# design.net
KiCad netlist of a schematic drawn in EasyEDA Pro
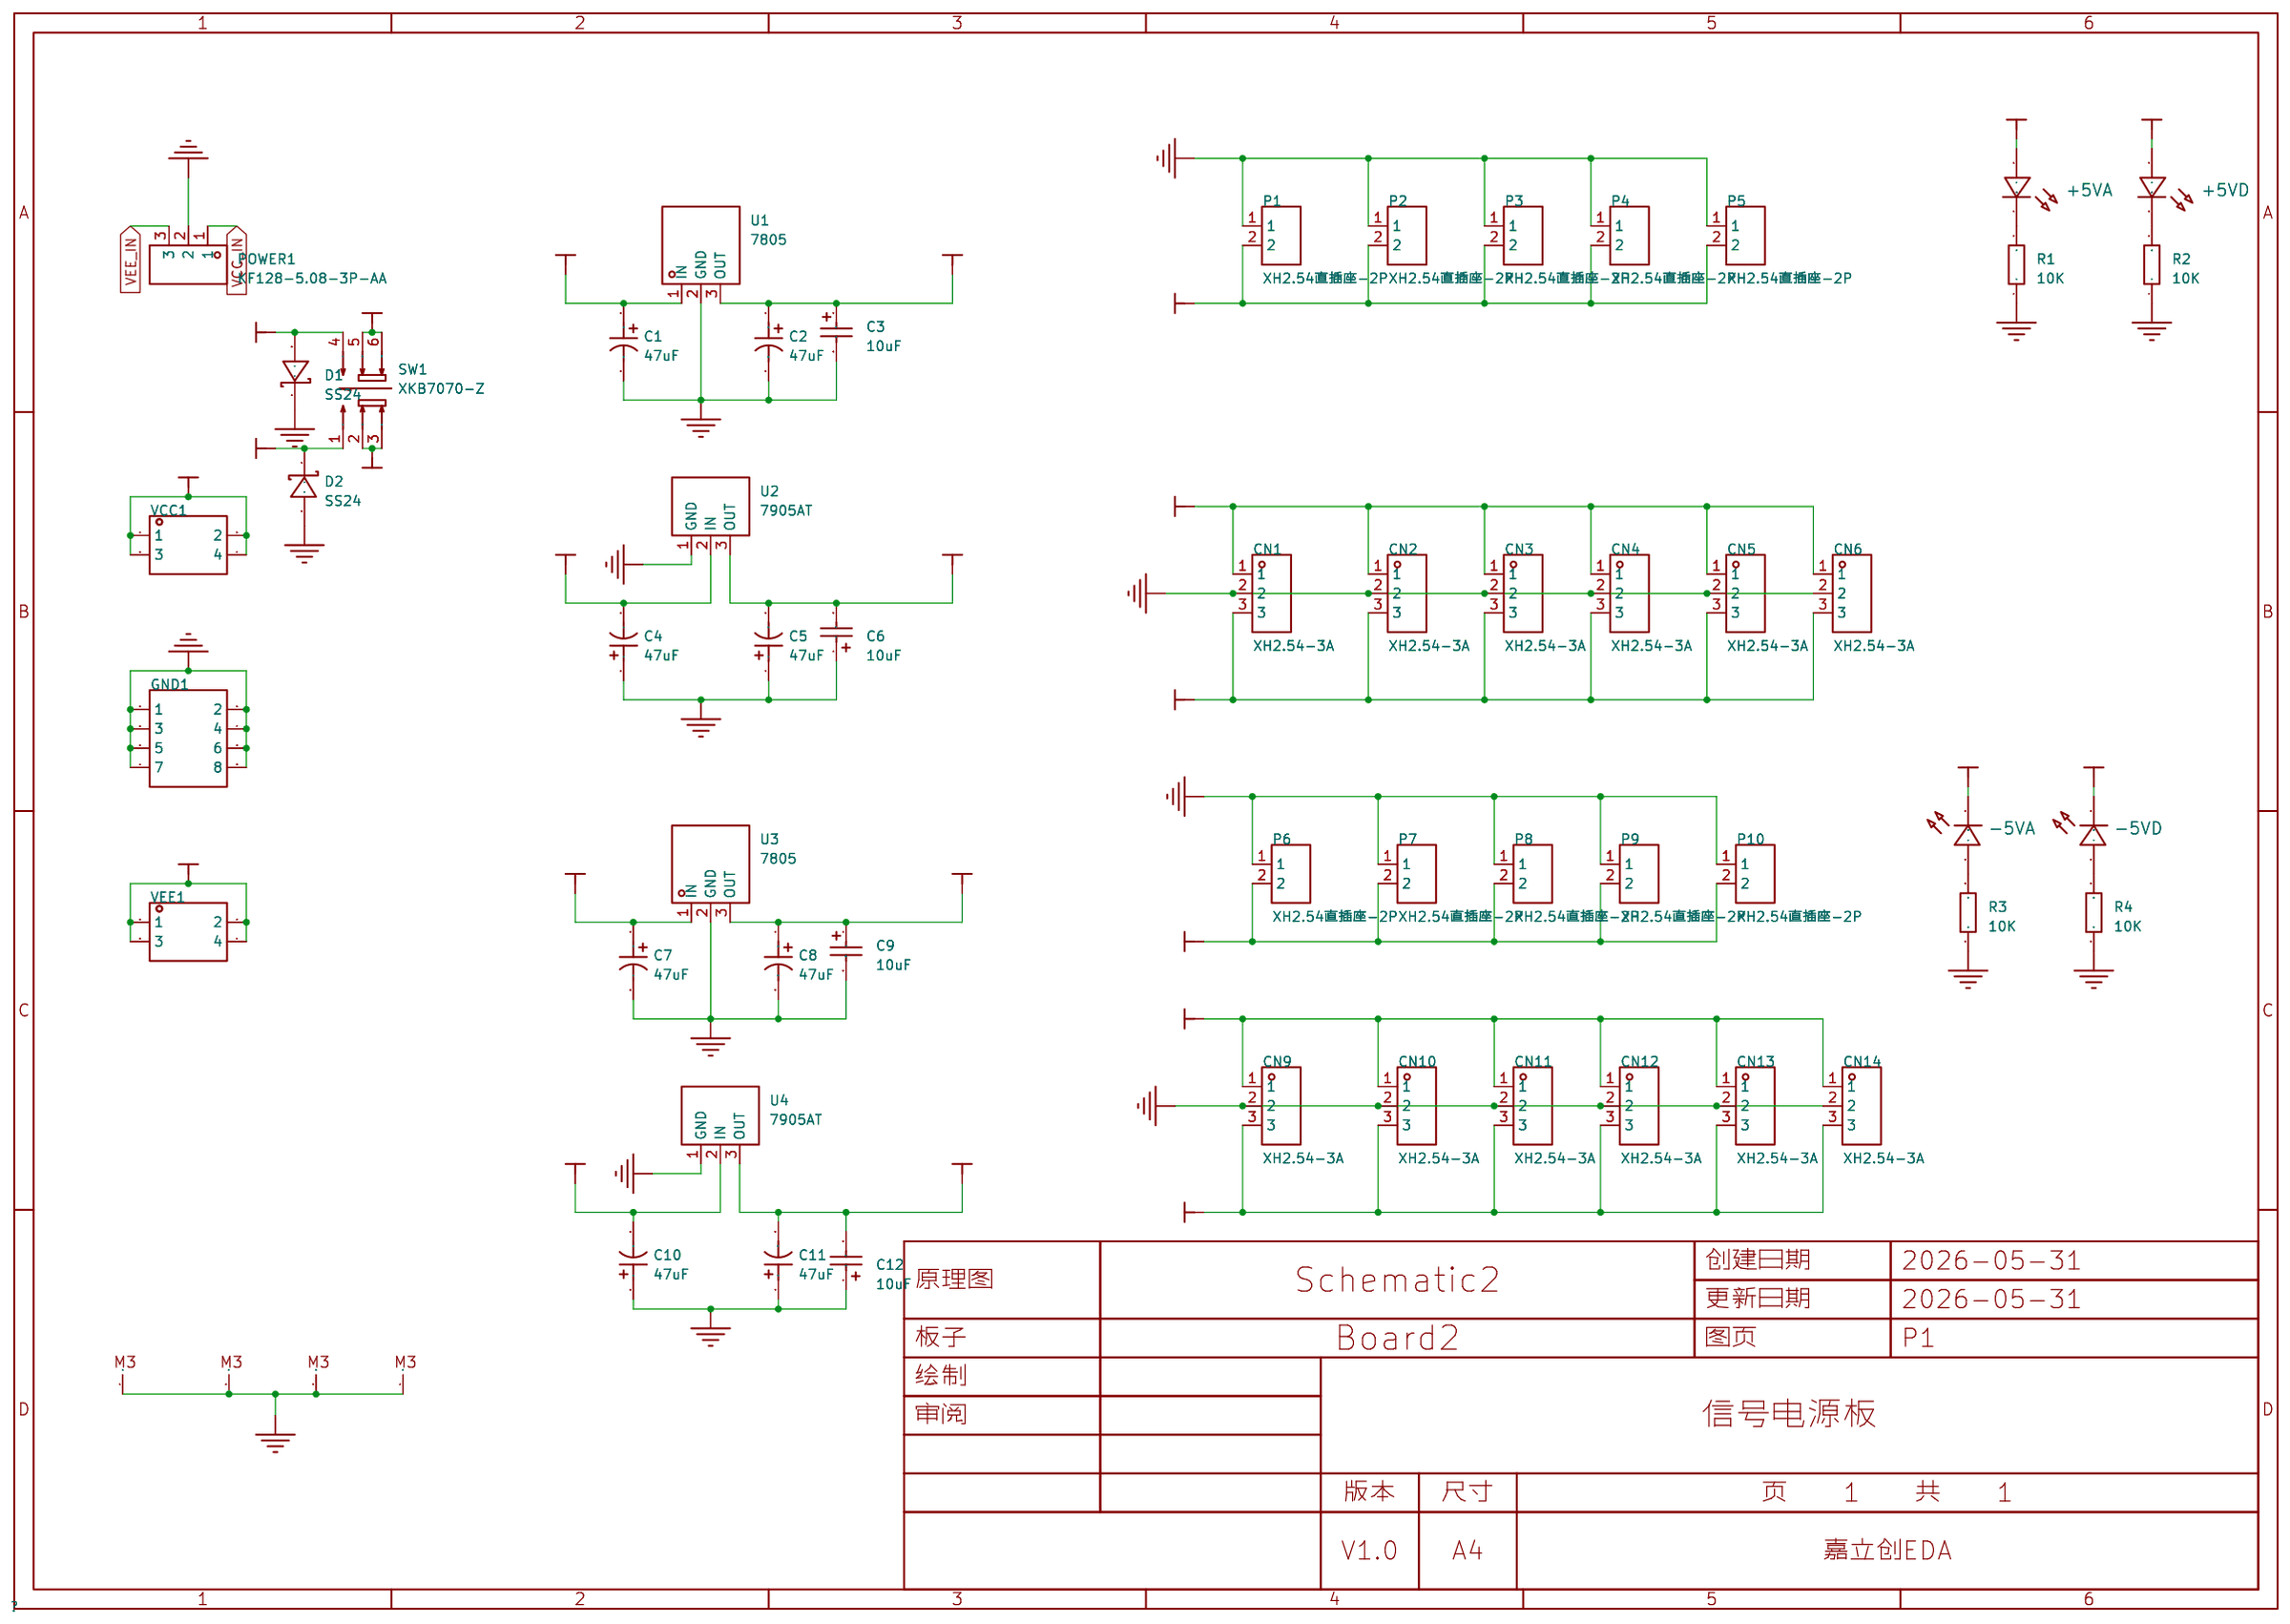
[diagram p0: schematic sheet]

(export (version "E")
  (design (tool "Eeschema 10.0.6"))
  (components
    (comp (ref "+5VA")
      (value "~")
      (footprint "easyedapro:LED_0603")
      (libsource (lib "easyedapro") (part "LED_R"))
    )
    (comp (ref "+5VD")
      (value "~")
      (footprint "easyedapro:LED_0603")
      (libsource (lib "easyedapro") (part "LED_R"))
    )
    (comp (ref "-5VA")
      (value "~")
      (footprint "easyedapro:LED_0603")
      (libsource (lib "easyedapro") (part "LED_R"))
    )
    (comp (ref "-5VD")
      (value "~")
      (footprint "easyedapro:LED_0603")
      (libsource (lib "easyedapro") (part "LED_R"))
    )
    (comp (ref "C1")
      (value "47uF")
      (footprint "easyedapro:CAP-SMD_BD6.3-L6.6-W6.6-LS7.3-FD")
      (fields (field (name "Manufacturer Part") "126RV0104") (field (name "Manufacturer") "KNSCHA(科尼盛)"))
      (libsource (lib "easyedapro") (part "126RV0104"))
    )
    (comp (ref "C2")
      (value "47uF")
      (footprint "easyedapro:CAP-SMD_BD6.3-L6.6-W6.6-LS7.3-FD")
      (fields (field (name "Manufacturer Part") "126RV0104") (field (name "Manufacturer") "KNSCHA(科尼盛)"))
      (libsource (lib "easyedapro") (part "126RV0104"))
    )
    (comp (ref "C3")
      (value "10uF")
      (footprint "easyedapro:CAP-SMD_L3.2-W1.6-RD-C7171")
      (fields (field (name "Manufacturer Part") "TAJA106K016RNJ") (field (name "Manufacturer") "Kyocera AVX"))
      (libsource (lib "easyedapro") (part "TAJA106K016RNJ"))
    )
    (comp (ref "C4")
      (value "47uF")
      (footprint "easyedapro:CAP-SMD_BD6.3-L6.6-W6.6-LS7.3-FD")
      (fields (field (name "Manufacturer Part") "126RV0104") (field (name "Manufacturer") "KNSCHA(科尼盛)"))
      (libsource (lib "easyedapro") (part "126RV0104"))
    )
    (comp (ref "C5")
      (value "47uF")
      (footprint "easyedapro:CAP-SMD_BD6.3-L6.6-W6.6-LS7.3-FD")
      (fields (field (name "Manufacturer Part") "126RV0104") (field (name "Manufacturer") "KNSCHA(科尼盛)"))
      (libsource (lib "easyedapro") (part "126RV0104"))
    )
    (comp (ref "C6")
      (value "10uF")
      (footprint "easyedapro:CAP-SMD_L3.2-W1.6-RD-C7171")
      (fields (field (name "Manufacturer Part") "TAJA106K016RNJ") (field (name "Manufacturer") "Kyocera AVX"))
      (libsource (lib "easyedapro") (part "TAJA106K016RNJ"))
    )
    (comp (ref "C7")
      (value "47uF")
      (footprint "easyedapro:CAP-SMD_BD6.3-L6.6-W6.6-LS7.3-FD")
      (fields (field (name "Manufacturer Part") "126RV0104") (field (name "Manufacturer") "KNSCHA(科尼盛)"))
      (libsource (lib "easyedapro") (part "126RV0104"))
    )
    (comp (ref "C8")
      (value "47uF")
      (footprint "easyedapro:CAP-SMD_BD6.3-L6.6-W6.6-LS7.3-FD")
      (fields (field (name "Manufacturer Part") "126RV0104") (field (name "Manufacturer") "KNSCHA(科尼盛)"))
      (libsource (lib "easyedapro") (part "126RV0104"))
    )
    (comp (ref "C9")
      (value "10uF")
      (footprint "easyedapro:CAP-SMD_L3.2-W1.6-RD-C7171")
      (fields (field (name "Manufacturer Part") "TAJA106K016RNJ") (field (name "Manufacturer") "Kyocera AVX"))
      (libsource (lib "easyedapro") (part "TAJA106K016RNJ"))
    )
    (comp (ref "C10")
      (value "47uF")
      (footprint "easyedapro:CAP-SMD_BD6.3-L6.6-W6.6-LS7.3-FD")
      (fields (field (name "Manufacturer Part") "126RV0104") (field (name "Manufacturer") "KNSCHA(科尼盛)"))
      (libsource (lib "easyedapro") (part "126RV0104"))
    )
    (comp (ref "C11")
      (value "47uF")
      (footprint "easyedapro:CAP-SMD_BD6.3-L6.6-W6.6-LS7.3-FD")
      (fields (field (name "Manufacturer Part") "126RV0104") (field (name "Manufacturer") "KNSCHA(科尼盛)"))
      (libsource (lib "easyedapro") (part "126RV0104"))
    )
    (comp (ref "C12")
      (value "10uF")
      (footprint "easyedapro:CAP-SMD_L3.2-W1.6-RD-C7171")
      (fields (field (name "Manufacturer Part") "TAJA106K016RNJ") (field (name "Manufacturer") "Kyocera AVX"))
      (libsource (lib "easyedapro") (part "TAJA106K016RNJ"))
    )
    (comp (ref "CN1")
      (value "XH2.54-3A")
      (footprint "easyedapro:CONN-TH_3P-P2.50_HCTL_XH-3A-L")
      (libsource (lib "easyedapro") (part "XH2.54-3A"))
    )
    (comp (ref "CN2")
      (value "XH2.54-3A")
      (footprint "easyedapro:CONN-TH_3P-P2.50_HCTL_XH-3A-L")
      (libsource (lib "easyedapro") (part "XH2.54-3A"))
    )
    (comp (ref "CN3")
      (value "XH2.54-3A")
      (footprint "easyedapro:CONN-TH_3P-P2.50_HCTL_XH-3A-L")
      (libsource (lib "easyedapro") (part "XH2.54-3A"))
    )
    (comp (ref "CN4")
      (value "XH2.54-3A")
      (footprint "easyedapro:CONN-TH_3P-P2.50_HCTL_XH-3A-L")
      (libsource (lib "easyedapro") (part "XH2.54-3A"))
    )
    (comp (ref "CN5")
      (value "XH2.54-3A")
      (footprint "easyedapro:CONN-TH_3P-P2.50_HCTL_XH-3A-L")
      (libsource (lib "easyedapro") (part "XH2.54-3A"))
    )
    (comp (ref "CN6")
      (value "XH2.54-3A")
      (footprint "easyedapro:CONN-TH_3P-P2.50_HCTL_XH-3A-L")
      (libsource (lib "easyedapro") (part "XH2.54-3A"))
    )
    (comp (ref "CN9")
      (value "XH2.54-3A")
      (footprint "easyedapro:CONN-TH_3P-P2.50_HCTL_XH-3A-L")
      (libsource (lib "easyedapro") (part "XH2.54-3A"))
    )
    (comp (ref "CN10")
      (value "XH2.54-3A")
      (footprint "easyedapro:CONN-TH_3P-P2.50_HCTL_XH-3A-L")
      (libsource (lib "easyedapro") (part "XH2.54-3A"))
    )
    (comp (ref "CN11")
      (value "XH2.54-3A")
      (footprint "easyedapro:CONN-TH_3P-P2.50_HCTL_XH-3A-L")
      (libsource (lib "easyedapro") (part "XH2.54-3A"))
    )
    (comp (ref "CN12")
      (value "XH2.54-3A")
      (footprint "easyedapro:CONN-TH_3P-P2.50_HCTL_XH-3A-L")
      (libsource (lib "easyedapro") (part "XH2.54-3A"))
    )
    (comp (ref "CN13")
      (value "XH2.54-3A")
      (footprint "easyedapro:CONN-TH_3P-P2.50_HCTL_XH-3A-L")
      (libsource (lib "easyedapro") (part "XH2.54-3A"))
    )
    (comp (ref "CN14")
      (value "XH2.54-3A")
      (footprint "easyedapro:CONN-TH_3P-P2.50_HCTL_XH-3A-L")
      (libsource (lib "easyedapro") (part "XH2.54-3A"))
    )
    (comp (ref "D1")
      (value "SS24")
      (footprint "easyedapro:SMA_L4.3-W2.6-LS5.2-RD")
      (description "正向压降(Vf):550mV@2A;直流反向耐压(Vr):40V;平均整流电流(Io):2A;")
      (libsource (lib "easyedapro") (part "SS24_C13444"))
    )
    (comp (ref "D2")
      (value "SS24")
      (footprint "easyedapro:SMA_L4.3-W2.6-LS5.2-RD")
      (description "正向压降(Vf):550mV@2A;直流反向耐压(Vr):40V;平均整流电流(Io):2A;")
      (libsource (lib "easyedapro") (part "SS24_C13444"))
    )
    (comp (ref "GND1")
      (value "~")
      (footprint "easyedapro:HDR-TH_8P-P2.54-V-F-R2-C4-S2.54-1")
      (libsource (lib "easyedapro") (part "HDR-F-2.54_2x4"))
    )
    (comp (ref "M1") (value "~") (footprint "easyedapro:M3") (libsource (lib "easyedapro") (part "螺丝孔")))
    (comp (ref "M2") (value "~") (footprint "easyedapro:M3") (libsource (lib "easyedapro") (part "螺丝孔")))
    (comp (ref "M3") (value "~") (footprint "easyedapro:M3") (libsource (lib "easyedapro") (part "螺丝孔")))
    (comp (ref "M4") (value "~") (footprint "easyedapro:M3") (libsource (lib "easyedapro") (part "螺丝孔")))
    (comp (ref "P1")
      (value "XH2.54直插座-2P")
      (footprint "easyedapro:CONN-TH_XH2.54-2P")
      (libsource (lib "easyedapro") (part "XH2.54直插座-2P"))
    )
    (comp (ref "P2")
      (value "XH2.54直插座-2P")
      (footprint "easyedapro:CONN-TH_XH2.54-2P")
      (libsource (lib "easyedapro") (part "XH2.54直插座-2P"))
    )
    (comp (ref "P3")
      (value "XH2.54直插座-2P")
      (footprint "easyedapro:CONN-TH_XH2.54-2P")
      (libsource (lib "easyedapro") (part "XH2.54直插座-2P"))
    )
    (comp (ref "P4")
      (value "XH2.54直插座-2P")
      (footprint "easyedapro:CONN-TH_XH2.54-2P")
      (libsource (lib "easyedapro") (part "XH2.54直插座-2P"))
    )
    (comp (ref "P5")
      (value "XH2.54直插座-2P")
      (footprint "easyedapro:CONN-TH_XH2.54-2P")
      (libsource (lib "easyedapro") (part "XH2.54直插座-2P"))
    )
    (comp (ref "P6")
      (value "XH2.54直插座-2P")
      (footprint "easyedapro:CONN-TH_XH2.54-2P")
      (libsource (lib "easyedapro") (part "XH2.54直插座-2P"))
    )
    (comp (ref "P7")
      (value "XH2.54直插座-2P")
      (footprint "easyedapro:CONN-TH_XH2.54-2P")
      (libsource (lib "easyedapro") (part "XH2.54直插座-2P"))
    )
    (comp (ref "P8")
      (value "XH2.54直插座-2P")
      (footprint "easyedapro:CONN-TH_XH2.54-2P")
      (libsource (lib "easyedapro") (part "XH2.54直插座-2P"))
    )
    (comp (ref "P9")
      (value "XH2.54直插座-2P")
      (footprint "easyedapro:CONN-TH_XH2.54-2P")
      (libsource (lib "easyedapro") (part "XH2.54直插座-2P"))
    )
    (comp (ref "P10")
      (value "XH2.54直插座-2P")
      (footprint "easyedapro:CONN-TH_XH2.54-2P")
      (libsource (lib "easyedapro") (part "XH2.54直插座-2P"))
    )
    (comp (ref "POWER1")
      (value "KF128-5.08-3P-AA")
      (footprint "easyedapro:CONN-TH_3P-P5.08_KF128-5.08-3P")
      (fields (field (name "Manufacturer") "KEFA(科发)"))
      (libsource (lib "easyedapro") (part "KF128-5.08-3P"))
    )
    (comp (ref "R1") (value "10K") (footprint "easyedapro:R0603") (libsource (lib "easyedapro") (part "电阻")))
    (comp (ref "R2") (value "10K") (footprint "easyedapro:R0603") (libsource (lib "easyedapro") (part "电阻")))
    (comp (ref "R3") (value "10K") (footprint "easyedapro:R0603") (libsource (lib "easyedapro") (part "电阻")))
    (comp (ref "R4") (value "10K") (footprint "easyedapro:R0603") (libsource (lib "easyedapro") (part "电阻")))
    (comp (ref "SW1")
      (value "XKB7070-Z")
      (footprint "easyedapro:SW-TH_6P-L7.0-W7.0-P2.00")
      (fields (field (name "Manufacturer") "XKB Connection(中国星坤)"))
      (libsource (lib "easyedapro") (part "XKB7070-Z"))
    )
    (comp (ref "U1")
      (value "7805")
      (footprint "easyedapro:TO-220-3_L10.2-W4.5-P2.54-L-1")
      (fields (field (name "Manufacturer") "SY(顺烨)"))
      (libsource (lib "easyedapro") (part "7805_C4944936"))
    )
    (comp (ref "U2")
      (value "7905AT")
      (footprint "easyedapro:TO-220AB-3_L10.1-W4.6-P2.54-L")
      (fields (field (name "Manufacturer") "YFW(佑风微)"))
      (libsource (lib "easyedapro") (part "7905AT"))
    )
    (comp (ref "U3")
      (value "7805")
      (footprint "easyedapro:TO-220-3_L10.2-W4.5-P2.54-L-1")
      (fields (field (name "Manufacturer") "SY(顺烨)"))
      (libsource (lib "easyedapro") (part "7805_C4944936"))
    )
    (comp (ref "U4")
      (value "7905AT")
      (footprint "easyedapro:TO-220AB-3_L10.1-W4.6-P2.54-L")
      (fields (field (name "Manufacturer") "YFW(佑风微)"))
      (libsource (lib "easyedapro") (part "7905AT"))
    )
    (comp (ref "VCC1")
      (value "~")
      (footprint "easyedapro:HDR-TH_4P-P2.54-V-F-R2-C2-S2.54")
      (libsource (lib "easyedapro") (part "HDR-F-2.54_2x2"))
    )
    (comp (ref "VEE1")
      (value "~")
      (footprint "easyedapro:HDR-TH_4P-P2.54-V-F-R2-C2-S2.54")
      (libsource (lib "easyedapro") (part "HDR-F-2.54_2x2"))
    )
  )
  (nets
    (net (code "1") (name "+5VA") (class "Default")
      (node (ref "+5VA") (pin "2") (pinfunction "A_2") (pintype "input"))
      (node (ref "C2") (pin "1") (pinfunction "1_1") (pintype "input"))
      (node (ref "C3") (pin "1") (pinfunction "1_1") (pintype "input"))
      (node (ref "CN1") (pin "1") (pinfunction "1_1") (pintype "unspecified"))
      (node (ref "CN2") (pin "1") (pinfunction "1_1") (pintype "unspecified"))
      (node (ref "CN3") (pin "1") (pinfunction "1_1") (pintype "unspecified"))
      (node (ref "CN4") (pin "1") (pinfunction "1_1") (pintype "unspecified"))
      (node (ref "CN5") (pin "1") (pinfunction "1_1") (pintype "unspecified"))
      (node (ref "CN6") (pin "1") (pinfunction "1_1") (pintype "unspecified"))
      (node (ref "P1") (pin "2") (pinfunction "2_2") (pintype "unspecified"))
      (node (ref "P2") (pin "2") (pinfunction "2_2") (pintype "unspecified"))
      (node (ref "P3") (pin "2") (pinfunction "2_2") (pintype "unspecified"))
      (node (ref "P4") (pin "2") (pinfunction "2_2") (pintype "unspecified"))
      (node (ref "P5") (pin "2") (pinfunction "2_2") (pintype "unspecified"))
      (node (ref "U1") (pin "3") (pinfunction "OUT_3") (pintype "unspecified"))
    )
    (net (code "2") (name "+5VD") (class "Default")
      (node (ref "+5VD") (pin "2") (pinfunction "A_2") (pintype "input"))
      (node (ref "C8") (pin "1") (pinfunction "1_1") (pintype "input"))
      (node (ref "C9") (pin "1") (pinfunction "1_1") (pintype "input"))
      (node (ref "CN10") (pin "1") (pinfunction "1_1") (pintype "unspecified"))
      (node (ref "CN11") (pin "1") (pinfunction "1_1") (pintype "unspecified"))
      (node (ref "CN12") (pin "1") (pinfunction "1_1") (pintype "unspecified"))
      (node (ref "CN13") (pin "1") (pinfunction "1_1") (pintype "unspecified"))
      (node (ref "CN14") (pin "1") (pinfunction "1_1") (pintype "unspecified"))
      (node (ref "CN9") (pin "1") (pinfunction "1_1") (pintype "unspecified"))
      (node (ref "P10") (pin "2") (pinfunction "2_2") (pintype "unspecified"))
      (node (ref "P6") (pin "2") (pinfunction "2_2") (pintype "unspecified"))
      (node (ref "P7") (pin "2") (pinfunction "2_2") (pintype "unspecified"))
      (node (ref "P8") (pin "2") (pinfunction "2_2") (pintype "unspecified"))
      (node (ref "P9") (pin "2") (pinfunction "2_2") (pintype "unspecified"))
      (node (ref "U3") (pin "3") (pinfunction "OUT_3") (pintype "unspecified"))
    )
    (net (code "3") (name "-5VA") (class "Default")
      (node (ref "-5VA") (pin "1") (pinfunction "C_1") (pintype "input"))
      (node (ref "C5") (pin "2") (pinfunction "2_2") (pintype "input"))
      (node (ref "C6") (pin "2") (pinfunction "2_2") (pintype "input"))
      (node (ref "CN1") (pin "3") (pinfunction "3_3") (pintype "unspecified"))
      (node (ref "CN2") (pin "3") (pinfunction "3_3") (pintype "unspecified"))
      (node (ref "CN3") (pin "3") (pinfunction "3_3") (pintype "unspecified"))
      (node (ref "CN4") (pin "3") (pinfunction "3_3") (pintype "unspecified"))
      (node (ref "CN5") (pin "3") (pinfunction "3_3") (pintype "unspecified"))
      (node (ref "CN6") (pin "3") (pinfunction "3_3") (pintype "unspecified"))
      (node (ref "U2") (pin "3") (pinfunction "OUT_3") (pintype "unspecified"))
    )
    (net (code "4") (name "-5VD") (class "Default")
      (node (ref "-5VD") (pin "1") (pinfunction "C_1") (pintype "input"))
      (node (ref "C11") (pin "2") (pinfunction "2_2") (pintype "input"))
      (node (ref "C12") (pin "2") (pinfunction "2_2") (pintype "input"))
      (node (ref "CN10") (pin "3") (pinfunction "3_3") (pintype "unspecified"))
      (node (ref "CN11") (pin "3") (pinfunction "3_3") (pintype "unspecified"))
      (node (ref "CN12") (pin "3") (pinfunction "3_3") (pintype "unspecified"))
      (node (ref "CN13") (pin "3") (pinfunction "3_3") (pintype "unspecified"))
      (node (ref "CN14") (pin "3") (pinfunction "3_3") (pintype "unspecified"))
      (node (ref "CN9") (pin "3") (pinfunction "3_3") (pintype "unspecified"))
      (node (ref "U4") (pin "3") (pinfunction "OUT_3") (pintype "unspecified"))
    )
    (net (code "5") (name "GND") (class "Default")
      (node (ref "C1") (pin "2") (pinfunction "2_2") (pintype "input"))
      (node (ref "C10") (pin "1") (pinfunction "1_1") (pintype "input"))
      (node (ref "C11") (pin "1") (pinfunction "1_1") (pintype "input"))
      (node (ref "C12") (pin "1") (pinfunction "1_1") (pintype "input"))
      (node (ref "C2") (pin "2") (pinfunction "2_2") (pintype "input"))
      (node (ref "C3") (pin "2") (pinfunction "2_2") (pintype "input"))
      (node (ref "C4") (pin "1") (pinfunction "1_1") (pintype "input"))
      (node (ref "C5") (pin "1") (pinfunction "1_1") (pintype "input"))
      (node (ref "C6") (pin "1") (pinfunction "1_1") (pintype "input"))
      (node (ref "C7") (pin "2") (pinfunction "2_2") (pintype "input"))
      (node (ref "C8") (pin "2") (pinfunction "2_2") (pintype "input"))
      (node (ref "C9") (pin "2") (pinfunction "2_2") (pintype "input"))
      (node (ref "CN1") (pin "2") (pinfunction "2_2") (pintype "unspecified"))
      (node (ref "CN10") (pin "2") (pinfunction "2_2") (pintype "unspecified"))
      (node (ref "CN11") (pin "2") (pinfunction "2_2") (pintype "unspecified"))
      (node (ref "CN12") (pin "2") (pinfunction "2_2") (pintype "unspecified"))
      (node (ref "CN13") (pin "2") (pinfunction "2_2") (pintype "unspecified"))
      (node (ref "CN14") (pin "2") (pinfunction "2_2") (pintype "unspecified"))
      (node (ref "CN2") (pin "2") (pinfunction "2_2") (pintype "unspecified"))
      (node (ref "CN3") (pin "2") (pinfunction "2_2") (pintype "unspecified"))
      (node (ref "CN4") (pin "2") (pinfunction "2_2") (pintype "unspecified"))
      (node (ref "CN5") (pin "2") (pinfunction "2_2") (pintype "unspecified"))
      (node (ref "CN6") (pin "2") (pinfunction "2_2") (pintype "unspecified"))
      (node (ref "CN9") (pin "2") (pinfunction "2_2") (pintype "unspecified"))
      (node (ref "D1") (pin "1") (pinfunction "K_1") (pintype "unspecified"))
      (node (ref "D2") (pin "2") (pinfunction "A_2") (pintype "unspecified"))
      (node (ref "GND1") (pin "1") (pinfunction "1_1") (pintype "input"))
      (node (ref "GND1") (pin "2") (pinfunction "2_2") (pintype "input"))
      (node (ref "GND1") (pin "3") (pinfunction "3_3") (pintype "input"))
      (node (ref "GND1") (pin "4") (pinfunction "4_4") (pintype "input"))
      (node (ref "GND1") (pin "5") (pinfunction "5_5") (pintype "input"))
      (node (ref "GND1") (pin "6") (pinfunction "6_6") (pintype "input"))
      (node (ref "GND1") (pin "7") (pinfunction "7_7") (pintype "input"))
      (node (ref "GND1") (pin "8") (pinfunction "8_8") (pintype "input"))
      (node (ref "M1") (pin "1") (pinfunction "1_1") (pintype "input"))
      (node (ref "M2") (pin "1") (pinfunction "1_1") (pintype "input"))
      (node (ref "M3") (pin "1") (pinfunction "1_1") (pintype "input"))
      (node (ref "M4") (pin "1") (pinfunction "1_1") (pintype "input"))
      (node (ref "P1") (pin "1") (pinfunction "1_1") (pintype "unspecified"))
      (node (ref "P10") (pin "1") (pinfunction "1_1") (pintype "unspecified"))
      (node (ref "P2") (pin "1") (pinfunction "1_1") (pintype "unspecified"))
      (node (ref "P3") (pin "1") (pinfunction "1_1") (pintype "unspecified"))
      (node (ref "P4") (pin "1") (pinfunction "1_1") (pintype "unspecified"))
      (node (ref "P5") (pin "1") (pinfunction "1_1") (pintype "unspecified"))
      (node (ref "P6") (pin "1") (pinfunction "1_1") (pintype "unspecified"))
      (node (ref "P7") (pin "1") (pinfunction "1_1") (pintype "unspecified"))
      (node (ref "P8") (pin "1") (pinfunction "1_1") (pintype "unspecified"))
      (node (ref "P9") (pin "1") (pinfunction "1_1") (pintype "unspecified"))
      (node (ref "POWER1") (pin "2") (pinfunction "2_2") (pintype "unspecified"))
      (node (ref "R1") (pin "1") (pinfunction "1_1") (pintype "input"))
      (node (ref "R2") (pin "1") (pinfunction "1_1") (pintype "input"))
      (node (ref "R3") (pin "1") (pinfunction "1_1") (pintype "input"))
      (node (ref "R4") (pin "1") (pinfunction "1_1") (pintype "input"))
      (node (ref "U1") (pin "2") (pinfunction "GND_2") (pintype "unspecified"))
      (node (ref "U2") (pin "1") (pinfunction "GND_1") (pintype "unspecified"))
      (node (ref "U3") (pin "2") (pinfunction "GND_2") (pintype "unspecified"))
      (node (ref "U4") (pin "1") (pinfunction "GND_1") (pintype "unspecified"))
    )
    (net (code "6") (name "Net-(+5VA-C)") (class "Default")
      (node (ref "+5VA") (pin "1") (pinfunction "C_1") (pintype "input"))
      (node (ref "R1") (pin "2") (pinfunction "2_2") (pintype "input"))
    )
    (net (code "7") (name "Net-(+5VD-C)") (class "Default")
      (node (ref "+5VD") (pin "1") (pinfunction "C_1") (pintype "input"))
      (node (ref "R2") (pin "2") (pinfunction "2_2") (pintype "input"))
    )
    (net (code "8") (name "Net-(-5VA-A)") (class "Default")
      (node (ref "-5VA") (pin "2") (pinfunction "A_2") (pintype "input"))
      (node (ref "R3") (pin "2") (pinfunction "2_2") (pintype "input"))
    )
    (net (code "9") (name "Net-(-5VD-A)") (class "Default")
      (node (ref "-5VD") (pin "2") (pinfunction "A_2") (pintype "input"))
      (node (ref "R4") (pin "2") (pinfunction "2_2") (pintype "input"))
    )
    (net (code "10") (name "VCC") (class "Default")
      (node (ref "C1") (pin "1") (pinfunction "1_1") (pintype "input"))
      (node (ref "C7") (pin "1") (pinfunction "1_1") (pintype "input"))
      (node (ref "D1") (pin "2") (pinfunction "A_2") (pintype "unspecified"))
      (node (ref "SW1") (pin "4") (pinfunction "4_4") (pintype "unspecified"))
      (node (ref "U1") (pin "1") (pinfunction "IN_1") (pintype "unspecified"))
      (node (ref "U3") (pin "1") (pinfunction "IN_1") (pintype "unspecified"))
    )
    (net (code "11") (name "VCC_IN") (class "Default")
      (node (ref "POWER1") (pin "1") (pinfunction "1_1") (pintype "unspecified"))
      (node (ref "SW1") (pin "5") (pinfunction "5_5") (pintype "unspecified"))
      (node (ref "SW1") (pin "6") (pinfunction "6_6") (pintype "unspecified"))
      (node (ref "VEE1") (pin "1") (pinfunction "1_1") (pintype "input"))
      (node (ref "VEE1") (pin "2") (pinfunction "2_2") (pintype "input"))
      (node (ref "VEE1") (pin "3") (pinfunction "3_3") (pintype "input"))
      (node (ref "VEE1") (pin "4") (pinfunction "4_4") (pintype "input"))
    )
    (net (code "12") (name "VEE") (class "Default")
      (node (ref "C10") (pin "2") (pinfunction "2_2") (pintype "input"))
      (node (ref "C4") (pin "2") (pinfunction "2_2") (pintype "input"))
      (node (ref "D2") (pin "1") (pinfunction "K_1") (pintype "unspecified"))
      (node (ref "SW1") (pin "1") (pinfunction "1_1") (pintype "unspecified"))
      (node (ref "U2") (pin "2") (pinfunction "IN_2") (pintype "unspecified"))
      (node (ref "U4") (pin "2") (pinfunction "IN_2") (pintype "unspecified"))
    )
    (net (code "13") (name "VEE_IN") (class "Default")
      (node (ref "POWER1") (pin "3") (pinfunction "3_3") (pintype "unspecified"))
      (node (ref "SW1") (pin "2") (pinfunction "2_2") (pintype "unspecified"))
      (node (ref "SW1") (pin "3") (pinfunction "3_3") (pintype "unspecified"))
      (node (ref "VCC1") (pin "1") (pinfunction "1_1") (pintype "input"))
      (node (ref "VCC1") (pin "2") (pinfunction "2_2") (pintype "input"))
      (node (ref "VCC1") (pin "3") (pinfunction "3_3") (pintype "input"))
      (node (ref "VCC1") (pin "4") (pinfunction "4_4") (pintype "input"))
    )
  )
)
